# TrinketCarV2.net
KiCad netlist of a schematic drawn in EAGLE
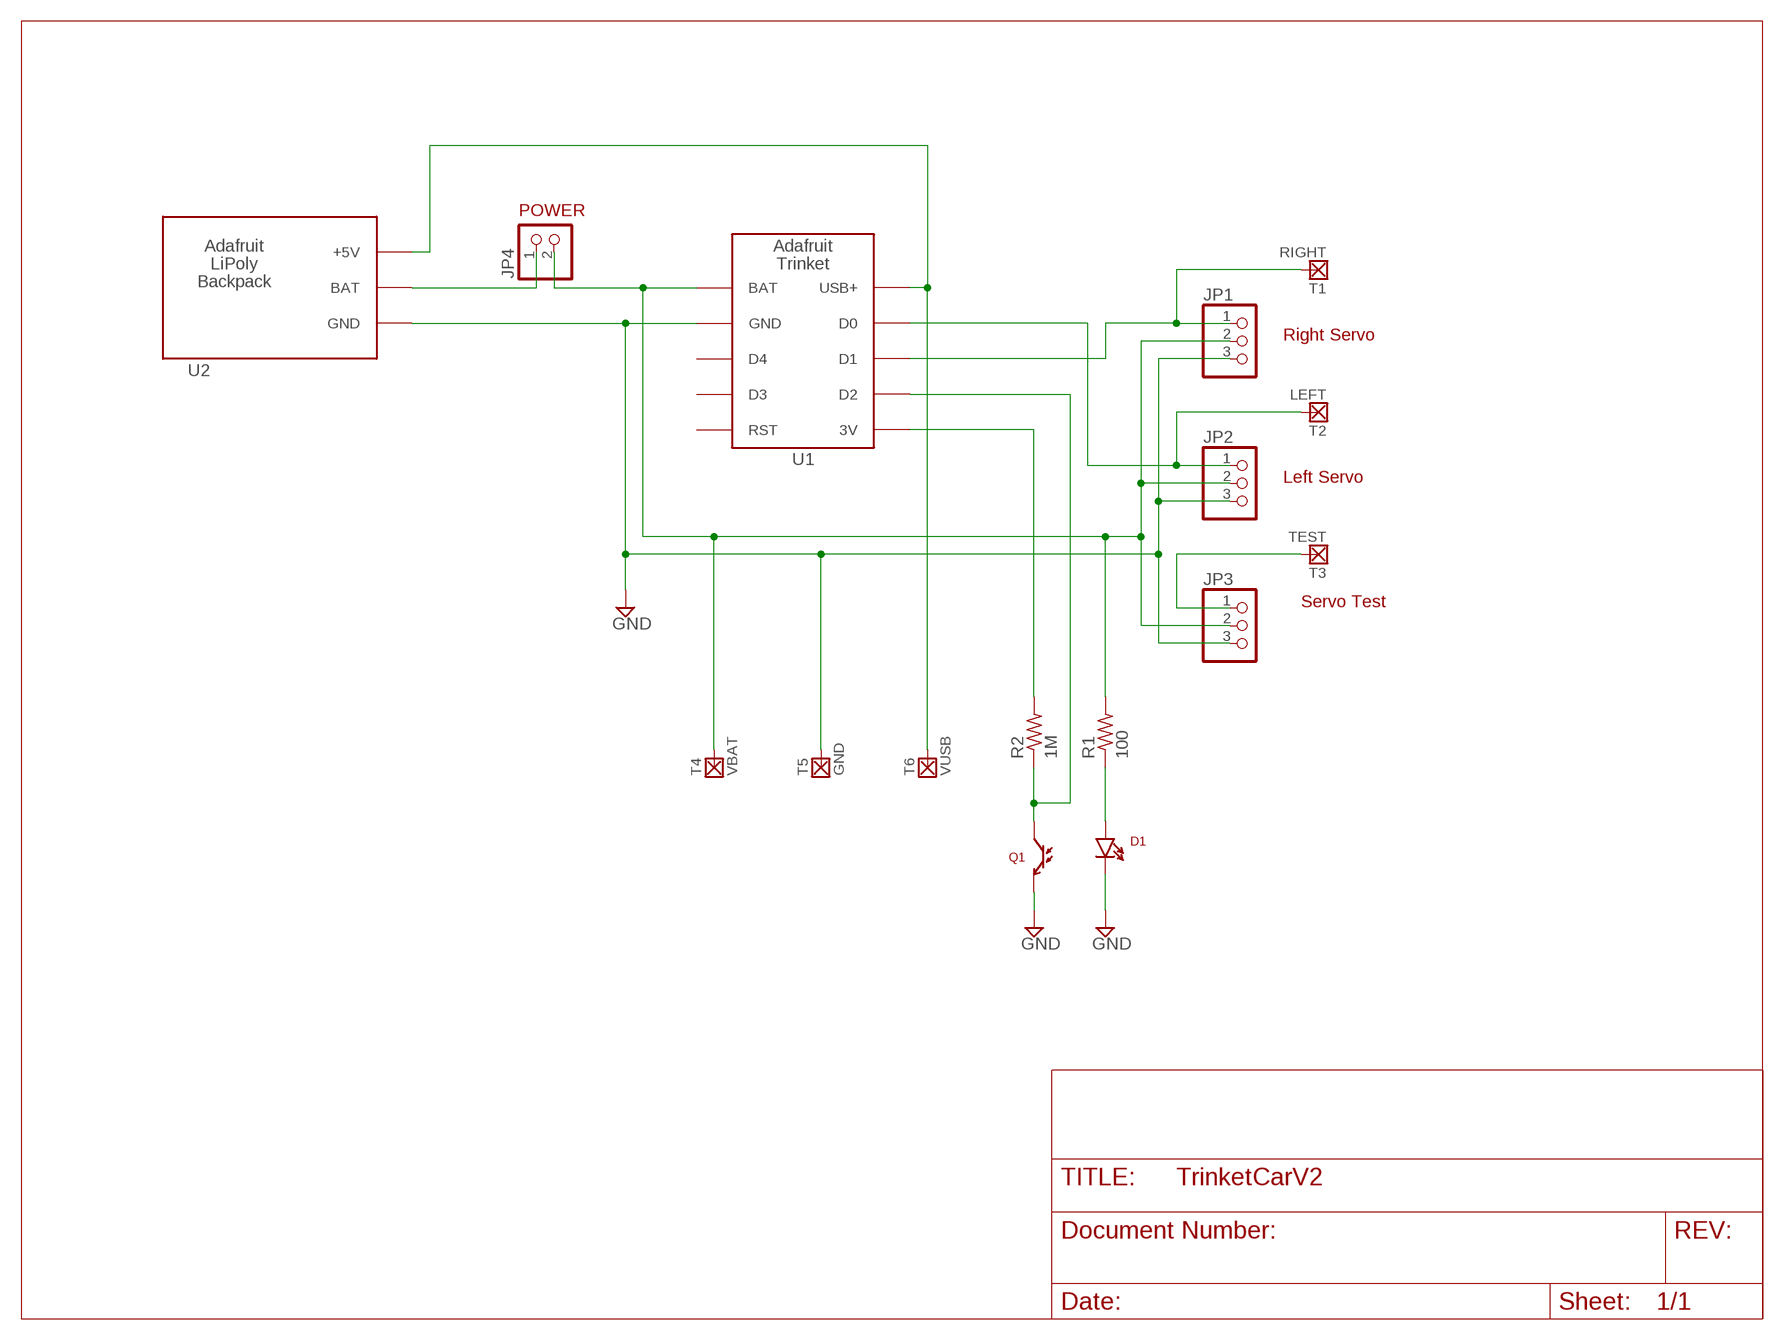
[diagram p0: schematic, sheet 1]

(export (version "E")
  (design (tool "Eeschema 10.0.6"))
  (components
    (comp (ref "D1")
      (value "LTE-302")
      (footprint "eagle-import:LTE-302")
      (libsource (lib "eagle-import") (part "LTE-302"))
    )
    (comp (ref "JP1")
      (value "PINHD-1X3")
      (footprint "eagle-import:1X03")
      (libsource (lib "eagle-import") (part "PINHD-1X3"))
    )
    (comp (ref "JP2")
      (value "PINHD-1X3")
      (footprint "eagle-import:1X03")
      (libsource (lib "eagle-import") (part "PINHD-1X3"))
    )
    (comp (ref "JP3")
      (value "PINHD-1X3")
      (footprint "eagle-import:1X03")
      (libsource (lib "eagle-import") (part "PINHD-1X3"))
    )
    (comp (ref "JP4")
      (value "PINHD-1X2")
      (footprint "eagle-import:1X02")
      (libsource (lib "eagle-import") (part "PINHD-1X2"))
    )
    (comp (ref "Q1")
      (value "LTR-301")
      (footprint "eagle-import:LTR-301")
      (libsource (lib "eagle-import") (part "LTR-301"))
    )
    (comp (ref "R1")
      (value "100")
      (footprint "eagle-import:0207_12")
      (libsource (lib "eagle-import") (part "R-US_0207/12"))
    )
    (comp (ref "R2")
      (value "1M")
      (footprint "eagle-import:0207_12")
      (libsource (lib "eagle-import") (part "R-US_0207/12"))
    )
    (comp (ref "T1")
      (value "RIGHT")
      (footprint "eagle-import:TERMPAD-SMALL")
      (libsource (lib "eagle-import") (part "TERMPOSTS"))
    )
    (comp (ref "T2")
      (value "LEFT")
      (footprint "eagle-import:TERMPAD-SMALL")
      (libsource (lib "eagle-import") (part "TERMPOSTS"))
    )
    (comp (ref "T3")
      (value "TEST")
      (footprint "eagle-import:TERMPAD-SMALL")
      (libsource (lib "eagle-import") (part "TERMPOSTS"))
    )
    (comp (ref "T4")
      (value "VBAT")
      (footprint "eagle-import:TERMPAD-SMALL")
      (libsource (lib "eagle-import") (part "TERMPOSTS"))
    )
    (comp (ref "T5")
      (value "GND")
      (footprint "eagle-import:TERMPAD-SMALL")
      (libsource (lib "eagle-import") (part "TERMPOSTS"))
    )
    (comp (ref "T6")
      (value "VUSB")
      (footprint "eagle-import:TERMPAD-SMALL")
      (libsource (lib "eagle-import") (part "TERMPOSTS"))
    )
    (comp (ref "U1")
      (value "ADAFRUIT_TRINKET")
      (footprint "eagle-import:TRINKITMINI")
      (libsource (lib "eagle-import") (part "ADAFRUIT_TRINKET"))
    )
    (comp (ref "U2")
      (value "LIPOLY_BACKPACK")
      (footprint "eagle-import:TRINKET_LIPO_BACKPACK")
      (libsource (lib "eagle-import") (part "LIPOLY_BACKPACK"))
    )
  )
  (nets
    (net (code "1") (name "GND") (class "Default")
      (node (ref "D1") (pin "C") (pinfunction "C_C") (pintype "bidirectional"))
      (node (ref "JP1") (pin "3") (pinfunction "3_3") (pintype "passive"))
      (node (ref "JP2") (pin "3") (pinfunction "3_3") (pintype "passive"))
      (node (ref "JP3") (pin "3") (pinfunction "3_3") (pintype "passive"))
      (node (ref "Q1") (pin "E") (pinfunction "E_E") (pintype "bidirectional"))
      (node (ref "T5") (pin "P$1") (pinfunction "P_P$1") (pintype "passive"))
      (node (ref "U1") (pin "P$2") (pinfunction "GND_P$2") (pintype "bidirectional"))
      (node (ref "U2") (pin "P$2") (pinfunction "GND_P$2") (pintype "bidirectional"))
    )
    (net (code "2") (name "Net-(D1-PadA)") (class "Default")
      (node (ref "D1") (pin "A") (pinfunction "A_A") (pintype "bidirectional"))
      (node (ref "R1") (pin "1") (pinfunction "1_1") (pintype "passive"))
    )
    (net (code "3") (name "Net-(T1-P)") (class "Default")
      (node (ref "JP1") (pin "1") (pinfunction "1_1") (pintype "passive"))
      (node (ref "T1") (pin "P$1") (pinfunction "P_P$1") (pintype "passive"))
      (node (ref "U1") (pin "P$8") (pinfunction "D1_P$8") (pintype "bidirectional"))
    )
    (net (code "4") (name "Net-(T2-P)") (class "Default")
      (node (ref "JP2") (pin "1") (pinfunction "1_1") (pintype "passive"))
      (node (ref "T2") (pin "P$1") (pinfunction "P_P$1") (pintype "passive"))
      (node (ref "U1") (pin "P$9") (pinfunction "D0_P$9") (pintype "bidirectional"))
    )
    (net (code "5") (name "Net-(T3-P)") (class "Default")
      (node (ref "JP3") (pin "1") (pinfunction "1_1") (pintype "passive"))
      (node (ref "T3") (pin "P$1") (pinfunction "P_P$1") (pintype "passive"))
    )
    (net (code "6") (name "Net-(T4-P)") (class "Default")
      (node (ref "JP1") (pin "2") (pinfunction "2_2") (pintype "passive"))
      (node (ref "JP2") (pin "2") (pinfunction "2_2") (pintype "passive"))
      (node (ref "JP3") (pin "2") (pinfunction "2_2") (pintype "passive"))
      (node (ref "JP4") (pin "2") (pinfunction "2_2") (pintype "passive"))
      (node (ref "R1") (pin "2") (pinfunction "2_2") (pintype "passive"))
      (node (ref "T4") (pin "P$1") (pinfunction "P_P$1") (pintype "passive"))
      (node (ref "U1") (pin "P$1") (pinfunction "BAT_P$1") (pintype "bidirectional"))
    )
    (net (code "7") (name "Net-(T6-P)") (class "Default")
      (node (ref "T6") (pin "P$1") (pinfunction "P_P$1") (pintype "passive"))
      (node (ref "U1") (pin "P$10") (pinfunction "USB+_P$10") (pintype "bidirectional"))
      (node (ref "U2") (pin "P$3") (pinfunction "+5V_P$3") (pintype "bidirectional"))
    )
    (net (code "8") (name "Net-(U1-3V)") (class "Default")
      (node (ref "R2") (pin "2") (pinfunction "2_2") (pintype "passive"))
      (node (ref "U1") (pin "P$6") (pinfunction "3V_P$6") (pintype "bidirectional"))
    )
    (net (code "9") (name "Net-(U1-D2)") (class "Default")
      (node (ref "Q1") (pin "C") (pinfunction "C_C") (pintype "bidirectional"))
      (node (ref "R2") (pin "1") (pinfunction "1_1") (pintype "passive"))
      (node (ref "U1") (pin "P$7") (pinfunction "D2_P$7") (pintype "bidirectional"))
    )
    (net (code "10") (name "Net-(U2-BAT)") (class "Default")
      (node (ref "JP4") (pin "1") (pinfunction "1_1") (pintype "passive"))
      (node (ref "U2") (pin "P$1") (pinfunction "BAT_P$1") (pintype "bidirectional"))
    )
    (net (code "11") (name "unconnected-(U1-D3-PadP$4)") (class "Default")
      (node (ref "U1") (pin "P$4") (pinfunction "D3_P$4") (pintype "bidirectional"))
    )
    (net (code "12") (name "unconnected-(U1-D4-PadP$3)") (class "Default")
      (node (ref "U1") (pin "P$3") (pinfunction "D4_P$3") (pintype "bidirectional"))
    )
    (net (code "13") (name "unconnected-(U1-RST-PadP$5)") (class "Default")
      (node (ref "U1") (pin "P$5") (pinfunction "RST_P$5") (pintype "bidirectional"))
    )
  )
)
